# 05_INERTIAL_SENSOR.net
KiCad netlist of a schematic drawn in Altium Designer
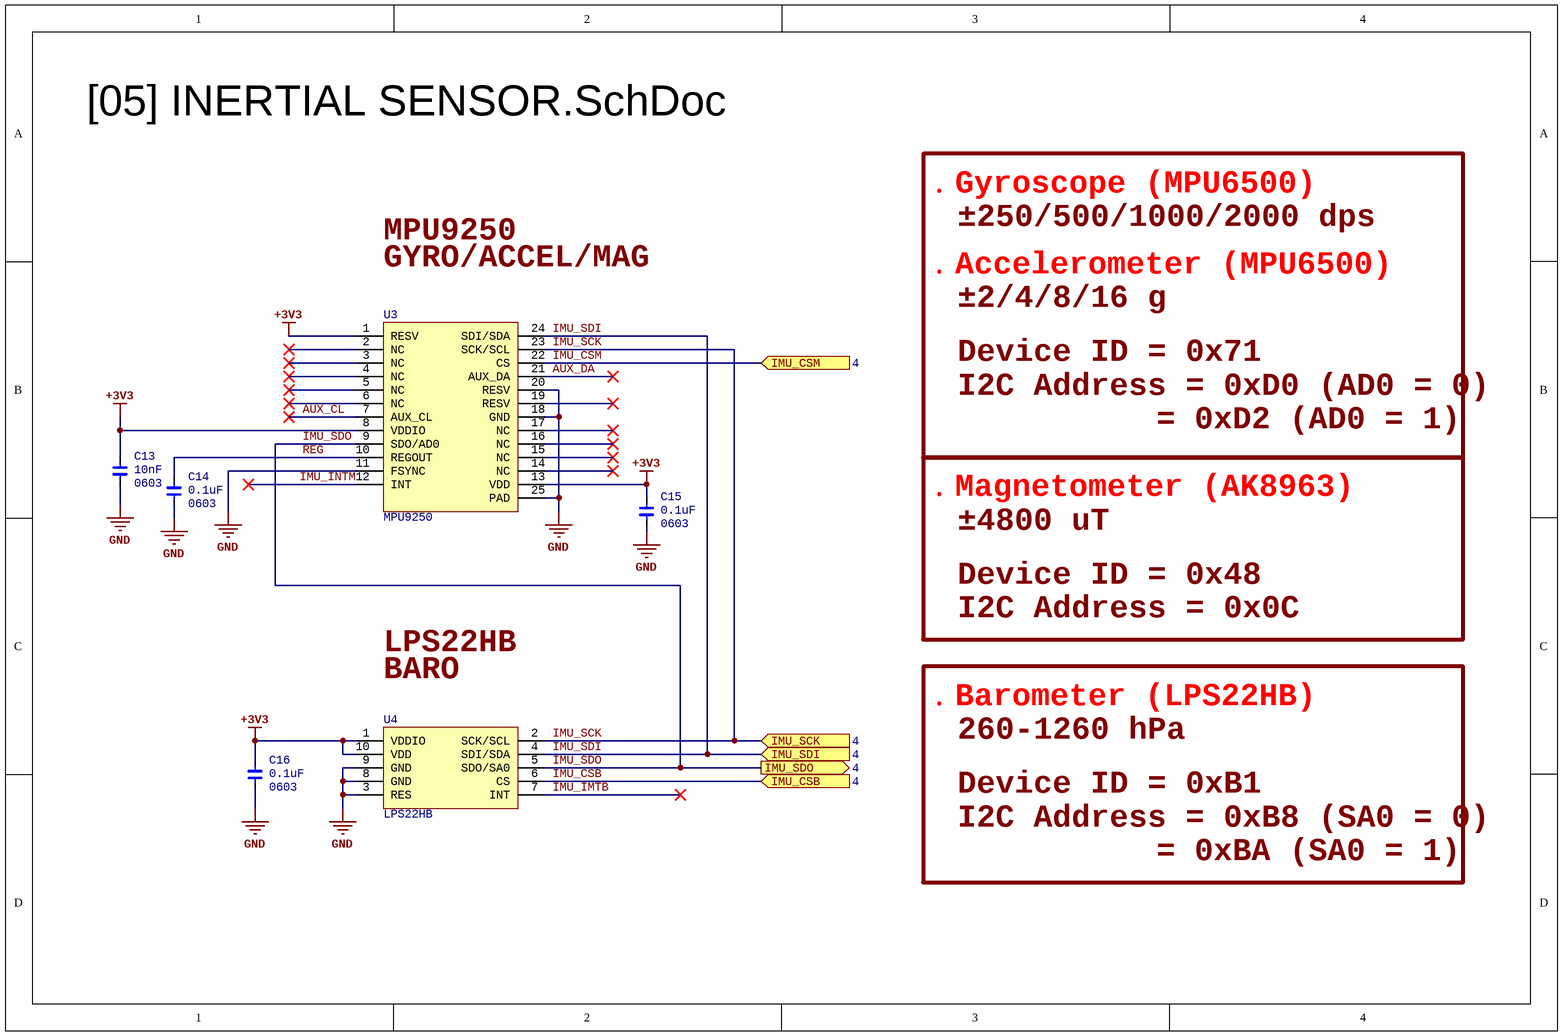
[diagram p0: [05] INERTIAL SENSOR.SchDoc]

(export (version "E")
  (design (tool "Eeschema 10.0.6"))
  (components
    (comp (ref "C13")
      (value "10nF")
      (footprint "PCB_PassiveCap:CAP_0603")
      (description "Capacitor")
      (fields (field (name "TYPE") "0603"))
      (libsource (lib "SCH_Passive") (part "Cap_0603"))
    )
    (comp (ref "C14")
      (value "0.1uF")
      (footprint "PCB_PassiveCap:CAP_0603")
      (description "Capacitor")
      (fields (field (name "TYPE") "0603"))
      (libsource (lib "SCH_Passive") (part "Cap_0603"))
    )
    (comp (ref "C15")
      (value "0.1uF")
      (footprint "PCB_PassiveCap:CAP_0603")
      (description "Capacitor")
      (fields (field (name "TYPE") "0603"))
      (libsource (lib "SCH_Passive") (part "Cap_0603"))
    )
    (comp (ref "C16")
      (value "0.1uF")
      (footprint "PCB_PassiveCap:CAP_0603")
      (description "Capacitor")
      (fields (field (name "TYPE") "0603"))
      (libsource (lib "SCH_Passive") (part "Cap_0603"))
    )
    (comp (ref "U3")
      (value "MPU9250")
      (footprint "PCB_IntegratedCircuit:QFN_P0.4_24")
      (description "Sensor Motion")
      (libsource (lib "SCH_IntegratedCircuit") (part "MPU925x"))
    )
    (comp (ref "U4")
      (value "LPS22HB")
      (footprint "PCB_IntegratedCircuit:HCLGA-2x2_10")
      (description "Sensor Pressure")
      (libsource (lib "SCH_IntegratedCircuit") (part "LPS22HB"))
    )
  )
  (nets
    (net (code "1") (name "+3V3") (class "Default")
      (node (ref "C13") (pin "2") (pinfunction "2_2") (pintype "passive"))
      (node (ref "C15") (pin "2") (pinfunction "2_2") (pintype "passive"))
      (node (ref "C16") (pin "2") (pinfunction "2_2") (pintype "passive"))
      (node (ref "U3") (pin "1") (pinfunction "RESV_1") (pintype "passive"))
      (node (ref "U3") (pin "13") (pinfunction "VDD_13") (pintype "passive"))
      (node (ref "U3") (pin "8") (pinfunction "VDDIO_8") (pintype "passive"))
      (node (ref "U4") (pin "1") (pinfunction "VDDIO_1") (pintype "passive"))
      (node (ref "U4") (pin "10") (pinfunction "VDD_10") (pintype "passive"))
    )
    (net (code "2") (name "/AUX_CL") (class "Default")
      (node (ref "U3") (pin "7") (pinfunction "AUX_CL_7") (pintype "passive+no_connect"))
    )
    (net (code "3") (name "/AUX_DA") (class "Default")
      (node (ref "U3") (pin "21") (pinfunction "AUX_DA_21") (pintype "passive+no_connect"))
    )
    (net (code "4") (name "/IMU_CSB") (class "Default")
      (node (ref "U4") (pin "6") (pinfunction "CS_6") (pintype "passive"))
    )
    (net (code "5") (name "/IMU_CSM") (class "Default")
      (node (ref "U3") (pin "22") (pinfunction "CS_22") (pintype "passive"))
    )
    (net (code "6") (name "/IMU_IMTB") (class "Default")
      (node (ref "U4") (pin "7") (pinfunction "INT_7") (pintype "passive+no_connect"))
    )
    (net (code "7") (name "/IMU_INTM") (class "Default")
      (node (ref "U3") (pin "12") (pinfunction "INT_12") (pintype "passive+no_connect"))
    )
    (net (code "8") (name "/IMU_SCK") (class "Default")
      (node (ref "U3") (pin "23") (pinfunction "SCK/SCL_23") (pintype "passive"))
      (node (ref "U4") (pin "2") (pinfunction "SCK/SCL_2") (pintype "passive"))
    )
    (net (code "9") (name "/IMU_SDI") (class "Default")
      (node (ref "U3") (pin "24") (pinfunction "SDI/SDA_24") (pintype "passive"))
      (node (ref "U4") (pin "4") (pinfunction "SDI/SDA_4") (pintype "passive"))
    )
    (net (code "10") (name "/IMU_SDO") (class "Default")
      (node (ref "U3") (pin "9") (pinfunction "SDO/AD0_9") (pintype "passive"))
      (node (ref "U4") (pin "5") (pinfunction "SDO/SA0_5") (pintype "passive"))
    )
    (net (code "11") (name "/REG") (class "Default")
      (node (ref "C14") (pin "2") (pinfunction "2_2") (pintype "passive"))
      (node (ref "U3") (pin "10") (pinfunction "REGOUT_10") (pintype "passive"))
    )
    (net (code "12") (name "GND") (class "Default")
      (node (ref "C13") (pin "1") (pinfunction "1_1") (pintype "passive"))
      (node (ref "C14") (pin "1") (pinfunction "1_1") (pintype "passive"))
      (node (ref "C15") (pin "1") (pinfunction "1_1") (pintype "passive"))
      (node (ref "C16") (pin "1") (pinfunction "1_1") (pintype "passive"))
      (node (ref "U3") (pin "11") (pinfunction "FSYNC_11") (pintype "passive"))
      (node (ref "U3") (pin "18") (pinfunction "GND_18") (pintype "passive"))
      (node (ref "U3") (pin "20") (pinfunction "RESV_20") (pintype "passive"))
      (node (ref "U3") (pin "25") (pinfunction "PAD_25") (pintype "passive"))
      (node (ref "U4") (pin "3") (pinfunction "RES_3") (pintype "passive"))
      (node (ref "U4") (pin "8") (pinfunction "GND_8") (pintype "passive"))
      (node (ref "U4") (pin "9") (pinfunction "GND_9") (pintype "passive"))
    )
    (net (code "13") (name "unconnected-(U3-NC-Pad2)") (class "Default")
      (node (ref "U3") (pin "2") (pinfunction "NC_2") (pintype "passive+no_connect"))
    )
    (net (code "14") (name "unconnected-(U3-NC-Pad3)") (class "Default")
      (node (ref "U3") (pin "3") (pinfunction "NC_3") (pintype "passive+no_connect"))
    )
    (net (code "15") (name "unconnected-(U3-NC-Pad4)") (class "Default")
      (node (ref "U3") (pin "4") (pinfunction "NC_4") (pintype "passive+no_connect"))
    )
    (net (code "16") (name "unconnected-(U3-NC-Pad5)") (class "Default")
      (node (ref "U3") (pin "5") (pinfunction "NC_5") (pintype "passive+no_connect"))
    )
    (net (code "17") (name "unconnected-(U3-NC-Pad6)") (class "Default")
      (node (ref "U3") (pin "6") (pinfunction "NC_6") (pintype "passive+no_connect"))
    )
    (net (code "18") (name "unconnected-(U3-NC-Pad14)") (class "Default")
      (node (ref "U3") (pin "14") (pinfunction "NC_14") (pintype "passive+no_connect"))
    )
    (net (code "19") (name "unconnected-(U3-NC-Pad15)") (class "Default")
      (node (ref "U3") (pin "15") (pinfunction "NC_15") (pintype "passive+no_connect"))
    )
    (net (code "20") (name "unconnected-(U3-NC-Pad16)") (class "Default")
      (node (ref "U3") (pin "16") (pinfunction "NC_16") (pintype "passive+no_connect"))
    )
    (net (code "21") (name "unconnected-(U3-NC-Pad17)") (class "Default")
      (node (ref "U3") (pin "17") (pinfunction "NC_17") (pintype "passive+no_connect"))
    )
    (net (code "22") (name "unconnected-(U3-RESV-Pad19)") (class "Default")
      (node (ref "U3") (pin "19") (pinfunction "RESV_19") (pintype "passive+no_connect"))
    )
  )
)
